# FTDI.net
KiCad netlist of a schematic drawn in Altium Designer
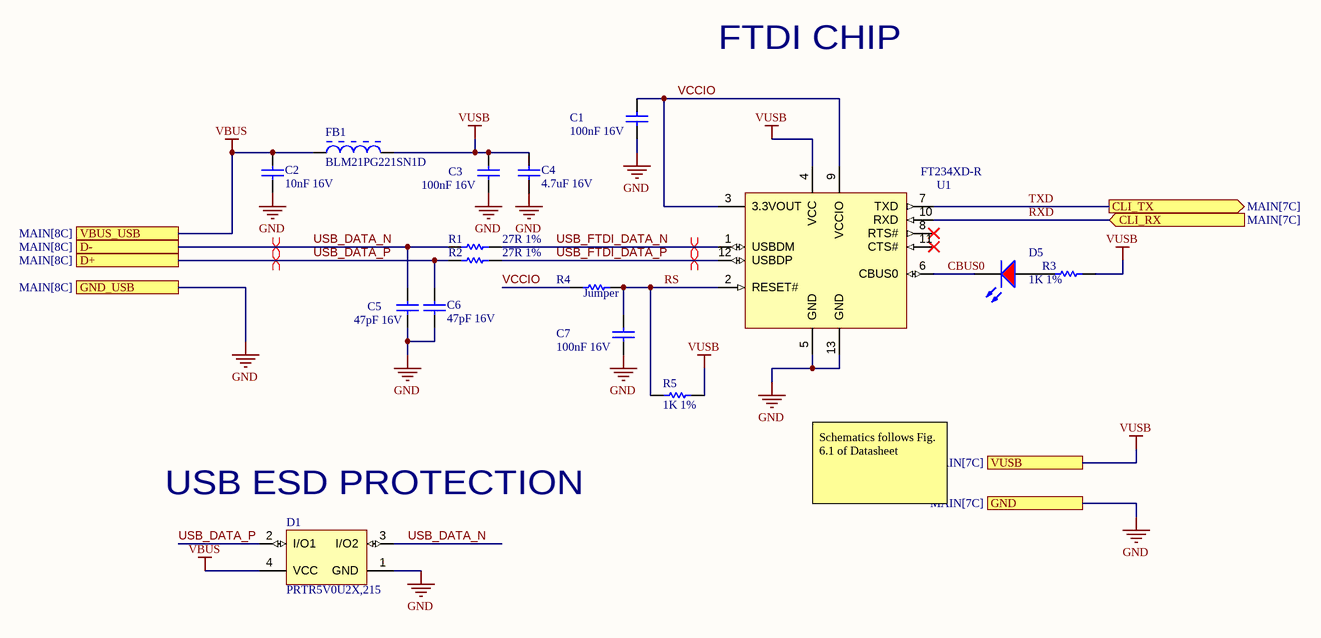
[diagram p0: FTDI.SchDoc]

(export (version "E")
  (design (tool "Eeschema 10.0.6"))
  (components
    (comp (ref "C1")
      (value "100nF 16V")
      (footprint "CAPC0603(1608)100_N")
      (description "CAP 100nF 16V ±10% 0603 (1608 Metric) Thickness 1mm SMD")
      (fields (field (name "TOLERANCE") "Â±10%"))
      (libsource (lib "Altium Content Vault") (part "CAP"))
    )
    (comp (ref "C2")
      (value "10nF 16V")
      (footprint "CAPC0603(1608)100_N")
      (description "CAP 10nF 16V ±10% 0603 (1608 Metric) Thickness 1mm SMD")
      (fields (field (name "TOLERANCE") "Â±10%"))
      (libsource (lib "Altium Content Vault") (part "CAP"))
    )
    (comp (ref "C3")
      (value "100nF 16V")
      (footprint "CAPC0603(1608)100_N")
      (description "CAP 100nF 16V ±10% 0603 (1608 Metric) Thickness 1mm SMD")
      (fields (field (name "TOLERANCE") "Â±10%"))
      (libsource (lib "Altium Content Vault") (part "CAP"))
    )
    (comp (ref "C4")
      (value "4.7uF 16V")
      (footprint "CAPC0805(2012)145_N")
      (description "CAP 4.7uF 16V -20% to +80% 0805 (2012 Metric) Thickness 1.45mm SMD")
      (fields (field (name "TOLERANCE") "-20% to +80%"))
      (libsource (lib "Altium Content Vault") (part "CAP"))
    )
    (comp (ref "C5")
      (value "47pF 16V")
      (footprint "CAPC0603(1608)100_N")
      (description "CAP 47pF 16V ±0.5pF 0603 (1608 Metric) Thickness 1mm SMD")
      (fields (field (name "TOLERANCE") "Â±0.5pF"))
      (libsource (lib "Altium Content Vault") (part "CAP"))
    )
    (comp (ref "C6")
      (value "47pF 16V")
      (footprint "CAPC0603(1608)100_N")
      (description "CAP 47pF 16V ±0.5pF 0603 (1608 Metric) Thickness 1mm SMD")
      (fields (field (name "TOLERANCE") "Â±0.5pF"))
      (libsource (lib "Altium Content Vault") (part "CAP"))
    )
    (comp (ref "C7")
      (value "100nF 16V")
      (footprint "CAPC0603(1608)100_N")
      (description "CAP 100nF 16V ±10% 0603 (1608 Metric) Thickness 1mm SMD")
      (fields (field (name "TOLERANCE") "Â±10%"))
      (libsource (lib "Altium Content Vault") (part "CAP"))
    )
    (comp (ref "D1")
      (value "PRTR5V0U2X,215")
      (footprint "NXP-SOT143B-4_V")
      (fields (field (name "MANUFACTURER") "NXP Semiconductors"))
      (libsource (lib "Altium Content Vault") (part "NXP-PRTR5V0U2X,215-4"))
    )
    (comp (ref "D5")
      (value "LTST-C170CKT")
      (footprint "LTST-C170CKT_V")
      (description "LED Uni-Color Red, 100 mW, 200 mA, -55 to 85 degC, 2-Pin SMD, RoHS, Tape and Reel")
      (fields (field (name "MANUFACTURER") "Lite-On"))
      (libsource (lib "Altium Content Vault") (part "LED-RED-AK-2"))
    )
    (comp (ref "FB1")
      (value "BLM21PG221SN1D")
      (footprint "MURA-BLM21-B20-CHIP-2_V2")
      (fields (field (name "MANUFACTURER") "Murata"))
      (libsource (lib "Altium Content Vault") (part "MURA-FB-2"))
    )
    (comp (ref "R1")
      (value "27R 1%")
      (footprint "RESC0603(1608)_N")
      (description "27R 0.1W 1% 0603 (1608 Metric)  SMD")
      (fields (field (name "TOLERANCE") "1 %") (field (name "POWER") "0.1 W"))
      (libsource (lib "Altium Content Vault") (part "RES"))
    )
    (comp (ref "R2")
      (value "27R 1%")
      (footprint "RESC0603(1608)_N")
      (description "27R 0.1W 1% 0603 (1608 Metric)  SMD")
      (fields (field (name "TOLERANCE") "1 %") (field (name "POWER") "0.1 W"))
      (libsource (lib "Altium Content Vault") (part "RES"))
    )
    (comp (ref "R3")
      (value "1K 1%")
      (footprint "RESC0603(1608)_N")
      (description "1K 0.1W 1% 0603 (1608 Metric)  SMD")
      (fields (field (name "TOLERANCE") "1 %") (field (name "POWER") "0.1 W"))
      (libsource (lib "Altium Content Vault") (part "RES"))
    )
    (comp (ref "R4")
      (value "Jumper")
      (footprint "RESC0603(1608)_N")
      (description "Jumper 0603 (1608 Metric)")
      (fields (field (name "POWER") "None"))
      (libsource (lib "Altium Content Vault") (part "RES"))
    )
    (comp (ref "R5")
      (value "1K 1%")
      (footprint "RESC0603(1608)_N")
      (description "1K 0.1W 1% 0603 (1608 Metric)  SMD")
      (fields (field (name "TOLERANCE") "1 %") (field (name "POWER") "0.1 W"))
      (libsource (lib "Altium Content Vault") (part "RES"))
    )
    (comp (ref "U1")
      (value "FT234XD-R")
      (footprint "DFN-12_V")
      (description "FT234XD USB to BASIC UART IC, -40 to +85 degC, 12-Pin DFN, Pb-Free, Tape and Reel")
      (fields (field (name "MANUFACTURER") "FTDI"))
      (libsource (lib "Altium Content Vault") (part "FTDI-FT234XD-DFN-12"))
    )
  )
  (nets
    (net (code "1") (name "/CBUS0") (class "Default")
      (node (ref "D5") (pin "2") (pinfunction "K_2") (pintype "passive"))
      (node (ref "U1") (pin "6") (pinfunction "CBUS0_6") (pintype "bidirectional"))
    )
    (net (code "2") (name "/RS") (class "Default")
      (node (ref "C7") (pin "2") (pinfunction "2_2") (pintype "passive"))
      (node (ref "R4") (pin "2") (pinfunction "2_2") (pintype "passive"))
      (node (ref "R5") (pin "2") (pinfunction "2_2") (pintype "passive"))
      (node (ref "U1") (pin "2") (pinfunction "RESET#_2") (pintype "input"))
    )
    (net (code "3") (name "/RXD") (class "Default")
      (node (ref "U1") (pin "10") (pinfunction "RXD_10") (pintype "input"))
    )
    (net (code "4") (name "/TXD") (class "Default")
      (node (ref "U1") (pin "7") (pinfunction "TXD_7") (pintype "output"))
    )
    (net (code "5") (name "/USB_DATA_N") (class "Default")
      (node (ref "C5") (pin "2") (pinfunction "2_2") (pintype "passive"))
      (node (ref "D1") (pin "3") (pinfunction "I/O2_3") (pintype "bidirectional"))
      (node (ref "R1") (pin "1") (pinfunction "1_1") (pintype "passive"))
    )
    (net (code "6") (name "/USB_DATA_P") (class "Default")
      (node (ref "C6") (pin "2") (pinfunction "2_2") (pintype "passive"))
      (node (ref "D1") (pin "2") (pinfunction "I/O1_2") (pintype "bidirectional"))
      (node (ref "R2") (pin "1") (pinfunction "1_1") (pintype "passive"))
    )
    (net (code "7") (name "/USB_FTDI_DATA_N") (class "Default")
      (node (ref "R1") (pin "2") (pinfunction "2_2") (pintype "passive"))
      (node (ref "U1") (pin "1") (pinfunction "USBDM_1") (pintype "bidirectional"))
    )
    (net (code "8") (name "/USB_FTDI_DATA_P") (class "Default")
      (node (ref "R2") (pin "2") (pinfunction "2_2") (pintype "passive"))
      (node (ref "U1") (pin "12") (pinfunction "USBDP_12") (pintype "bidirectional"))
    )
    (net (code "9") (name "/VCCIO") (class "Default")
      (node (ref "C1") (pin "2") (pinfunction "2_2") (pintype "passive"))
      (node (ref "R4") (pin "1") (pinfunction "1_1") (pintype "passive"))
      (node (ref "U1") (pin "3") (pinfunction "3.3VOUT_3") (pintype "power_in"))
      (node (ref "U1") (pin "9") (pinfunction "VCCIO_9") (pintype "power_in"))
    )
    (net (code "10") (name "GND") (class "Default")
      (node (ref "C1") (pin "1") (pinfunction "1_1") (pintype "passive"))
      (node (ref "C2") (pin "1") (pinfunction "1_1") (pintype "passive"))
      (node (ref "C3") (pin "1") (pinfunction "1_1") (pintype "passive"))
      (node (ref "C4") (pin "1") (pinfunction "1_1") (pintype "passive"))
      (node (ref "C5") (pin "1") (pinfunction "1_1") (pintype "passive"))
      (node (ref "C6") (pin "1") (pinfunction "1_1") (pintype "passive"))
      (node (ref "C7") (pin "1") (pinfunction "1_1") (pintype "passive"))
      (node (ref "D1") (pin "1") (pinfunction "GND_1") (pintype "power_in"))
      (node (ref "U1") (pin "13") (pinfunction "GND_13") (pintype "power_in"))
      (node (ref "U1") (pin "5") (pinfunction "GND_5") (pintype "power_in"))
    )
    (net (code "11") (name "Net-(D5-A)") (class "Default")
      (node (ref "D5") (pin "1") (pinfunction "A_1") (pintype "passive"))
      (node (ref "R3") (pin "1") (pinfunction "1_1") (pintype "passive"))
    )
    (net (code "12") (name "VBUS") (class "Default")
      (node (ref "C2") (pin "2") (pinfunction "2_2") (pintype "passive"))
      (node (ref "D1") (pin "4") (pinfunction "VCC_4") (pintype "power_in"))
      (node (ref "FB1") (pin "1") (pinfunction "1_1") (pintype "passive"))
    )
    (net (code "13") (name "VUSB") (class "Default")
      (node (ref "C3") (pin "2") (pinfunction "2_2") (pintype "passive"))
      (node (ref "C4") (pin "2") (pinfunction "2_2") (pintype "passive"))
      (node (ref "FB1") (pin "2") (pinfunction "2_2") (pintype "passive"))
      (node (ref "R3") (pin "2") (pinfunction "2_2") (pintype "passive"))
      (node (ref "R5") (pin "1") (pinfunction "1_1") (pintype "passive"))
      (node (ref "U1") (pin "4") (pinfunction "VCC_4") (pintype "power_in"))
    )
    (net (code "14") (name "unconnected-(U1-CTS#-Pad11)") (class "Default")
      (node (ref "U1") (pin "11") (pinfunction "CTS#_11") (pintype "input+no_connect"))
    )
    (net (code "15") (name "unconnected-(U1-RTS#-Pad8)") (class "Default")
      (node (ref "U1") (pin "8") (pinfunction "RTS#_8") (pintype "output+no_connect"))
    )
  )
)
